# zxld400-9-leds-mk-1.net
KiCad netlist of a schematic drawn in EAGLE
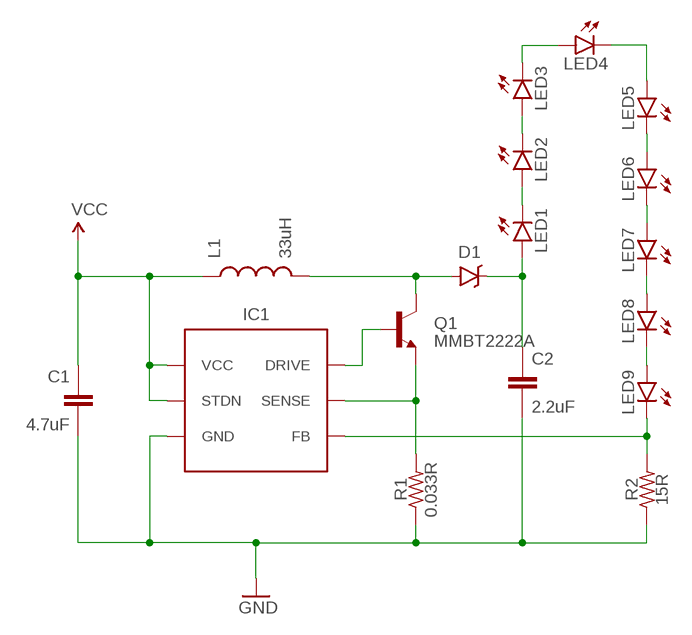
[diagram p0: schematic, sheet 1]

(export (version "E")
  (design (tool "Eeschema 10.0.6"))
  (components
    (comp (ref "C1")
      (value "4.7uF")
      (footprint "eagle-import:C0805")
      (libsource (lib "eagle-import") (part "CAPACITOR-CERAMICC0805"))
    )
    (comp (ref "C2")
      (value "2.2uF")
      (footprint "eagle-import:C0805")
      (libsource (lib "eagle-import") (part "CAPACITOR-CERAMICC0805"))
    )
    (comp (ref "D1")
      (value "DIODE-SCHOTTKYSMA")
      (footprint "eagle-import:SMA-DIODE-SCHOTTKY")
      (libsource (lib "eagle-import") (part "DIODE-SCHOTTKYSMA"))
    )
    (comp (ref "IC1")
      (value "ZXSC400")
      (footprint "eagle-import:SOT23-6")
      (libsource (lib "eagle-import") (part "ZXSC400"))
    )
    (comp (ref "L1")
      (value "33uH")
      (footprint "eagle-import:TAIYO-YUDEN-30XX")
      (libsource (lib "eagle-import") (part "INDUCTORTAIYO-YUDEN-30XX"))
    )
    (comp (ref "LED1")
      (value "LED5MM_SHORTPADS")
      (footprint "eagle-import:LED5MM_SHORTPADS")
      (libsource (lib "eagle-import") (part "LED5MM_SHORTPADS"))
    )
    (comp (ref "LED2")
      (value "LED5MM_SHORTPADS")
      (footprint "eagle-import:LED5MM_SHORTPADS")
      (libsource (lib "eagle-import") (part "LED5MM_SHORTPADS"))
    )
    (comp (ref "LED3")
      (value "LED5MM_SHORTPADS")
      (footprint "eagle-import:LED5MM_SHORTPADS")
      (libsource (lib "eagle-import") (part "LED5MM_SHORTPADS"))
    )
    (comp (ref "LED4")
      (value "LED5MM_SHORTPADS")
      (footprint "eagle-import:LED5MM_SHORTPADS")
      (libsource (lib "eagle-import") (part "LED5MM_SHORTPADS"))
    )
    (comp (ref "LED5")
      (value "LED5MM_SHORTPADS")
      (footprint "eagle-import:LED5MM_SHORTPADS")
      (libsource (lib "eagle-import") (part "LED5MM_SHORTPADS"))
    )
    (comp (ref "LED6")
      (value "LED5MM_SHORTPADS")
      (footprint "eagle-import:LED5MM_SHORTPADS")
      (libsource (lib "eagle-import") (part "LED5MM_SHORTPADS"))
    )
    (comp (ref "LED7")
      (value "LED5MM_SHORTPADS")
      (footprint "eagle-import:LED5MM_SHORTPADS")
      (libsource (lib "eagle-import") (part "LED5MM_SHORTPADS"))
    )
    (comp (ref "LED8")
      (value "LED5MM_SHORTPADS")
      (footprint "eagle-import:LED5MM_SHORTPADS")
      (libsource (lib "eagle-import") (part "LED5MM_SHORTPADS"))
    )
    (comp (ref "LED9")
      (value "LED5MM_SHORTPADS")
      (footprint "eagle-import:LED5MM_SHORTPADS")
      (libsource (lib "eagle-import") (part "LED5MM_SHORTPADS"))
    )
    (comp (ref "Q1")
      (value "MMBT2222A")
      (footprint "eagle-import:SOT23-3")
      (libsource (lib "eagle-import") (part "TRANSISTOR_NPNMMBT2222A"))
    )
    (comp (ref "R1")
      (value "0.033R")
      (footprint "eagle-import:R0805")
      (libsource (lib "eagle-import") (part "RESISTORR0805"))
    )
    (comp (ref "R2")
      (value "15R")
      (footprint "eagle-import:R0603")
      (libsource (lib "eagle-import") (part "RESISTORR0603"))
    )
  )
  (nets
    (net (code "1") (name "GND") (class "Default")
      (node (ref "C1") (pin "2") (pinfunction "2_2") (pintype "passive"))
      (node (ref "C2") (pin "2") (pinfunction "2_2") (pintype "passive"))
      (node (ref "IC1") (pin "2") (pinfunction "GND_2") (pintype "bidirectional"))
      (node (ref "R1") (pin "1") (pinfunction "1_1") (pintype "passive"))
      (node (ref "R2") (pin "1") (pinfunction "1_1") (pintype "passive"))
    )
    (net (code "2") (name "Net-(C2-Pad1)") (class "Default")
      (node (ref "C2") (pin "1") (pinfunction "1_1") (pintype "passive"))
      (node (ref "D1") (pin "C") (pinfunction "C_C") (pintype "passive"))
      (node (ref "LED1") (pin "A") (pinfunction "A_A") (pintype "passive"))
    )
    (net (code "3") (name "Net-(IC1-DRIVE)") (class "Default")
      (node (ref "IC1") (pin "6") (pinfunction "DRIVE_6") (pintype "bidirectional"))
      (node (ref "Q1") (pin "1") (pinfunction "B_1") (pintype "passive"))
    )
    (net (code "4") (name "Net-(IC1-FB)") (class "Default")
      (node (ref "IC1") (pin "5") (pinfunction "FB_5") (pintype "bidirectional"))
      (node (ref "LED9") (pin "K") (pinfunction "C_K") (pintype "passive"))
      (node (ref "R2") (pin "2") (pinfunction "2_2") (pintype "passive"))
    )
    (net (code "5") (name "Net-(IC1-SENSE)") (class "Default")
      (node (ref "IC1") (pin "4") (pinfunction "SENSE_4") (pintype "bidirectional"))
      (node (ref "Q1") (pin "2") (pinfunction "E_2") (pintype "passive"))
      (node (ref "R1") (pin "2") (pinfunction "2_2") (pintype "passive"))
    )
    (net (code "6") (name "Net-(LED1-C)") (class "Default")
      (node (ref "LED1") (pin "K") (pinfunction "C_K") (pintype "passive"))
      (node (ref "LED2") (pin "A") (pinfunction "A_A") (pintype "passive"))
    )
    (net (code "7") (name "Net-(LED2-C)") (class "Default")
      (node (ref "LED2") (pin "K") (pinfunction "C_K") (pintype "passive"))
      (node (ref "LED3") (pin "A") (pinfunction "A_A") (pintype "passive"))
    )
    (net (code "8") (name "Net-(LED3-C)") (class "Default")
      (node (ref "LED3") (pin "K") (pinfunction "C_K") (pintype "passive"))
      (node (ref "LED4") (pin "A") (pinfunction "A_A") (pintype "passive"))
    )
    (net (code "9") (name "Net-(LED4-C)") (class "Default")
      (node (ref "LED4") (pin "K") (pinfunction "C_K") (pintype "passive"))
      (node (ref "LED5") (pin "A") (pinfunction "A_A") (pintype "passive"))
    )
    (net (code "10") (name "Net-(LED5-C)") (class "Default")
      (node (ref "LED5") (pin "K") (pinfunction "C_K") (pintype "passive"))
      (node (ref "LED6") (pin "A") (pinfunction "A_A") (pintype "passive"))
    )
    (net (code "11") (name "Net-(LED6-C)") (class "Default")
      (node (ref "LED6") (pin "K") (pinfunction "C_K") (pintype "passive"))
      (node (ref "LED7") (pin "A") (pinfunction "A_A") (pintype "passive"))
    )
    (net (code "12") (name "Net-(LED7-C)") (class "Default")
      (node (ref "LED7") (pin "K") (pinfunction "C_K") (pintype "passive"))
      (node (ref "LED8") (pin "A") (pinfunction "A_A") (pintype "passive"))
    )
    (net (code "13") (name "Net-(LED8-C)") (class "Default")
      (node (ref "LED8") (pin "K") (pinfunction "C_K") (pintype "passive"))
      (node (ref "LED9") (pin "A") (pinfunction "A_A") (pintype "passive"))
    )
    (net (code "14") (name "Net-(Q1-C)") (class "Default")
      (node (ref "D1") (pin "A") (pinfunction "A_A") (pintype "passive"))
      (node (ref "L1") (pin "2") (pinfunction "2_2") (pintype "passive"))
      (node (ref "Q1") (pin "3") (pinfunction "C_3") (pintype "passive"))
    )
    (net (code "15") (name "VCC") (class "Default")
      (node (ref "C1") (pin "1") (pinfunction "1_1") (pintype "passive"))
      (node (ref "IC1") (pin "1") (pinfunction "VCC_1") (pintype "bidirectional"))
      (node (ref "IC1") (pin "3") (pinfunction "STDN_3") (pintype "bidirectional"))
      (node (ref "L1") (pin "1") (pinfunction "1_1") (pintype "passive"))
    )
  )
)
